# gateway.net
KiCad netlist of a schematic drawn in Altium Designer
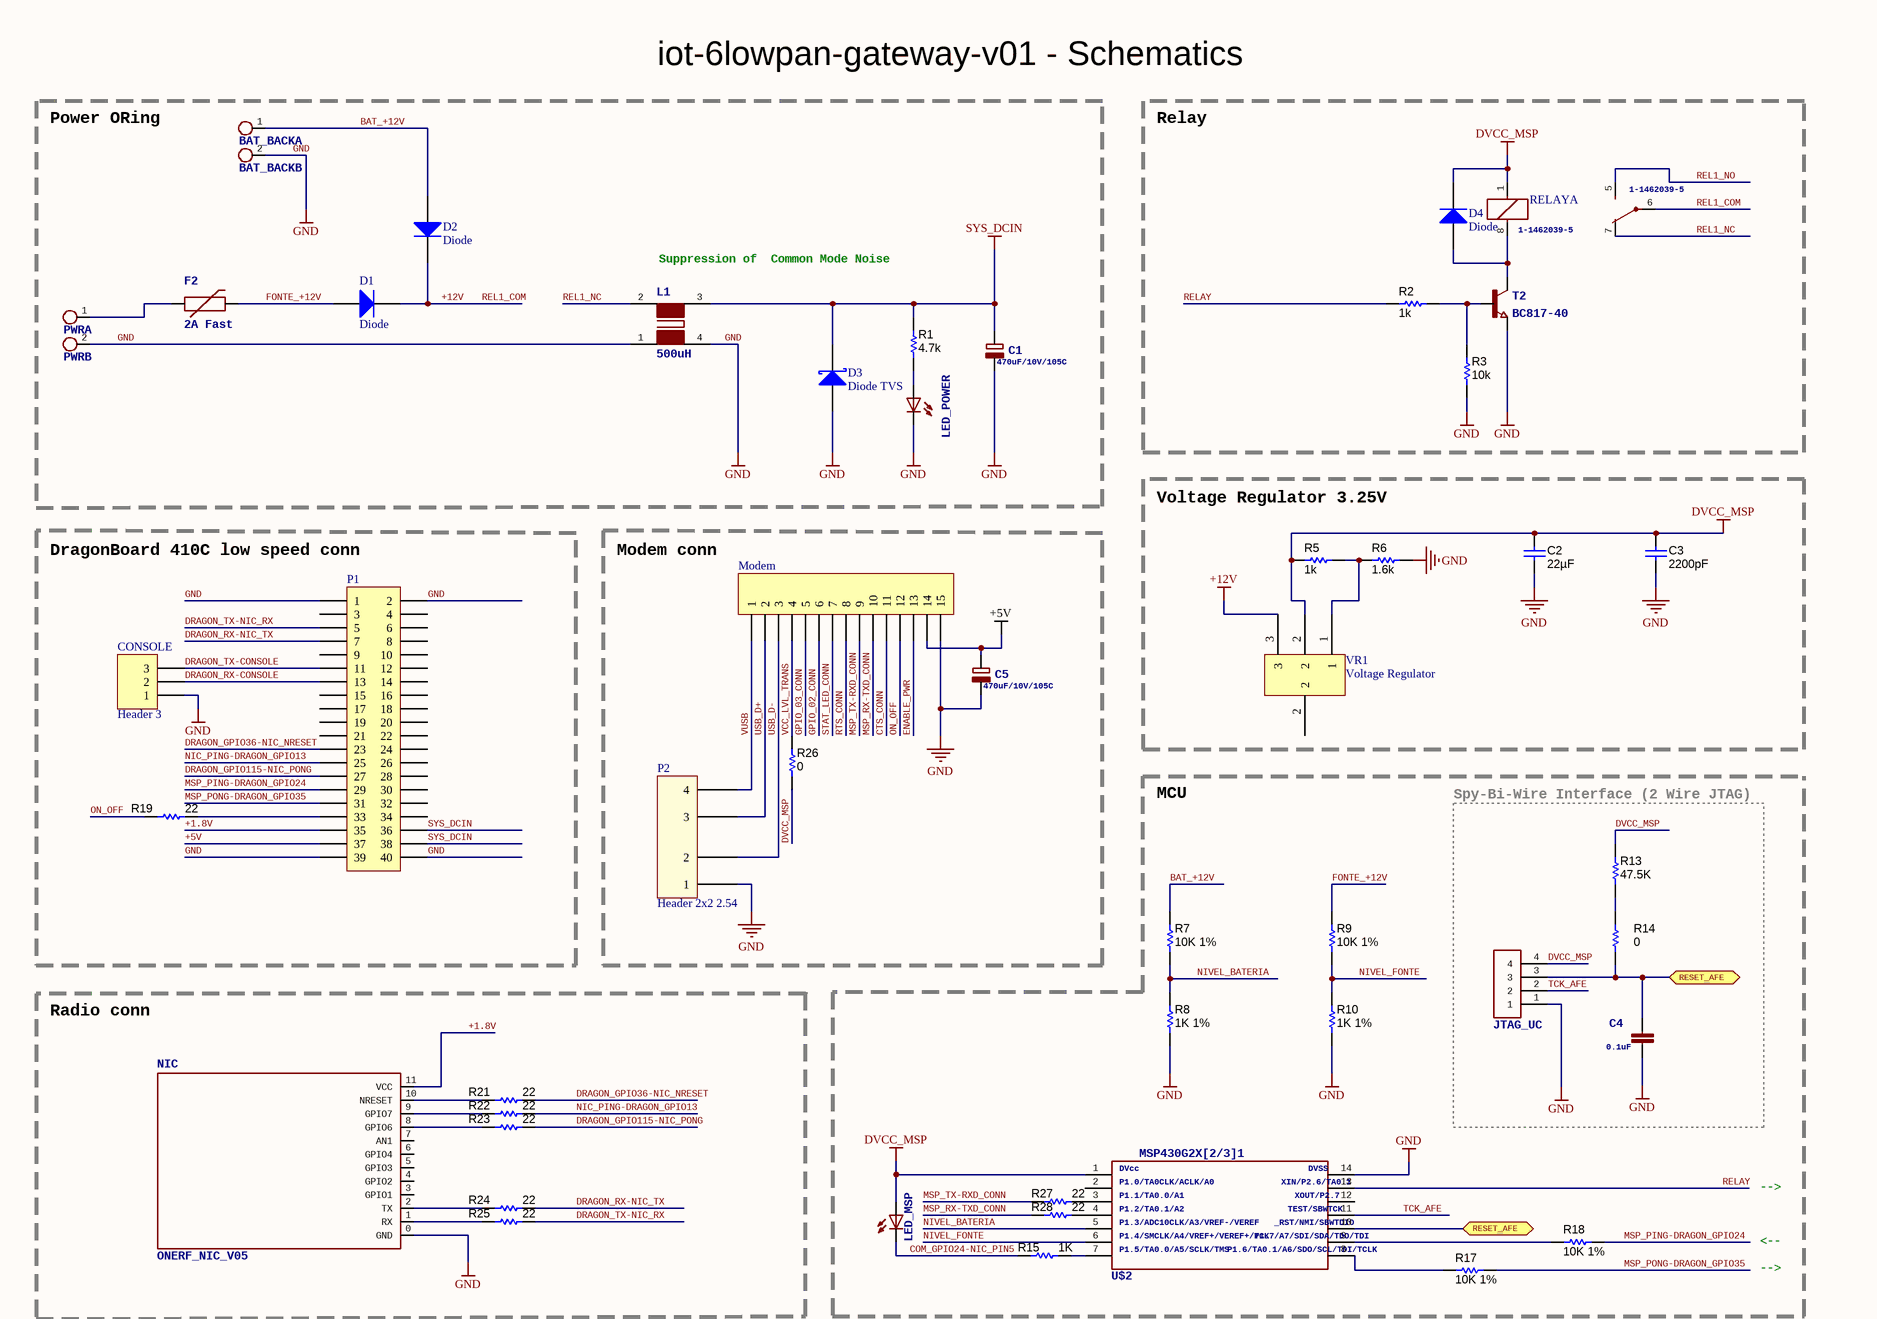
[diagram p0: gateway.SchDoc, top]
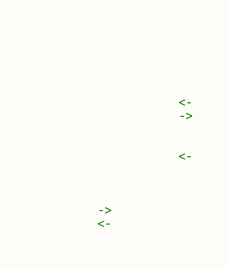
[diagram p1: gateway.SchDoc, bottom]

(export (version "E")
  (design (tool "Eeschema 10.0.6"))
  (components
    (comp (ref "BAT_BACK")
      (value "MKDSN1,5/2-5,08")
      (footprint "MKDSN1,5/2-5,08")
      (libsource (lib "Shield_Dragon") (part "MKDSN1,5/2-5,08"))
    )
    (comp (ref "C1")
      (value "470uF/10V/105C")
      (footprint "E2,5-6,3")
      (description "POLARIZED CAPACITOR, European symbol")
      (libsource (lib "oneRF_Base_COM_v04") (part "CPOL-EUE2.5-6.3"))
    )
    (comp (ref "C2")
      (value "C2012X5R1C226K125AC")
      (footprint "0805_HV")
      (description "CAP, CERM, 22 µF, 16 V, +/- 10%, X5R, 0805")
      (fields (field (name "VALUEDISPLAYED") "22µF"))
      (libsource (lib "Capacitor_Ceramic") (part "C2012X5R1C226K125AC"))
    )
    (comp (ref "C3")
      (value "CL10B222KB8SFNC")
      (footprint "0603")
      (description "CAP, CERM, 2200 pF, 50 V, +/- 10%, X7R, 0603")
      (fields (field (name "VALUEDISPLAYED") "2200pF") (field (name "PUBLISHER") "Texas Instruments"))
      (libsource (lib "altium-import") (part "root_3_C1005X7R1H222K_"))
    )
    (comp (ref "C4")
      (value "0.1uF")
      (footprint "0603")
      (description "CAPACITOR, European symbol")
      (libsource (lib "rcl") (part "C-EUC0603_DWS"))
    )
    (comp (ref "C5")
      (value "470uF/10V/105C")
      (footprint "E2,5-6,3")
      (description "POLARIZED CAPACITOR, European symbol")
      (libsource (lib "oneRF_Base_COM_v04") (part "CPOL-EUE2.5-6.3"))
    )
    (comp (ref "CONSOLE")
      (value "Header 3")
      (footprint "HDR1X3")
      (description "Header, 3-Pin")
      (fields (field (name "PUBLISHER") "Altium Limited"))
      (libsource (lib "Miscellaneous Connectors") (part "Header 3"))
    )
    (comp (ref "D1")
      (value "Diode")
      (footprint "SOD-80")
      (description "Diode, 100v, 1V, 200mA, -65º, 175º, SMT")
      (fields (field (name "PARTNUMBER") "FDLL4148_D87Z"))
      (libsource (lib "Miscellaneous Devices") (part "Diode"))
    )
    (comp (ref "D2")
      (value "Diode")
      (footprint "SOD-80")
      (description "Diode, 100v, 1V, 200mA, -65º, 175º, SMT")
      (fields (field (name "PARTNUMBER") "FDLL4148_D87Z"))
      (libsource (lib "Miscellaneous Devices") (part "Diode"))
    )
    (comp (ref "D3")
      (value "Diode TVS")
      (footprint "SMB")
      (description "Schottky Diode")
      (fields (field (name "PUBLISHER") "Altium Limited"))
      (libsource (lib "Miscellaneous Devices") (part "D Schottky"))
    )
    (comp (ref "D4")
      (value "Diode")
      (footprint "SOD-80")
      (description "Diode, 100v, 1V, 200mA, -65º, 175º, SMT")
      (fields (field (name "PARTNUMBER") "FDLL4148_D87Z"))
      (libsource (lib "Miscellaneous Devices") (part "Diode"))
    )
    (comp (ref "F2")
      (value "2A Fast")
      (footprint "C1206")
      (description "Resettable Fuse PTCResettable Fuse. Spark Fun Electronics SKU : COM-08357")
      (libsource (lib "SparkFun-PowerIC") (part "PTCSMD-W"))
    )
    (comp (ref "JTAG_UC")
      (value "CONECTOR_1X042.54MM")
      (footprint "HDR1X4")
      (libsource (lib "sparkFun2") (part "CONECTOR_1X042.54MM"))
    )
    (comp (ref "L1")
      (value "500uH")
      (footprint "WE-SL2_74422...")
      (libsource (lib "qualified_1") (part "WE-SL2"))
    )
    (comp (ref "LED_MSP")
      (value "LED/WHITE/0603")
      (footprint "LED0603")
      (libsource (lib "Shield_Dragon") (part "LED0603_WWS"))
    )
    (comp (ref "LED_POWER")
      (value "LED/Red/0603")
      (footprint "LED0603")
      (libsource (lib "Shield_Dragon") (part "LED0603DWS"))
    )
    (comp (ref "Modem")
      (value "oneRF_Modem_v01")
      (footprint "oneRF_Modem_v01")
      (description "CONN HEADER .100\" SNGL STR 15POS")
      (fields
        (field (name "MANUFACTURER") "Wurth Electronics Inc.")
        (field (name "MANUFACTURER PART NUMBER") "61301511121")
      )
      (libsource (lib "Schlib1 - copy") (part "Header 15"))
    )
    (comp (ref "NIC")
      (value "ONERF_NIC_V05")
      (footprint "ONERF_NIC_V05")
      (libsource (lib "oneRF_Base_COM_v04") (part "ONERF_NIC_V05"))
    )
    (comp (ref "P1")
      (value "Header 20X2")
      (footprint "HDR2X20")
      (description "Header, 20-Pin, Dual row")
      (fields (field (name "PUBLISHER") "Altium Limited"))
      (libsource (lib "Miscellaneous Connectors") (part "Header 20X2"))
    )
    (comp (ref "P2")
      (value "Header 2x2 2.54")
      (footprint "HEADER2x2(2.54)")
      (libsource (lib "Shield_Dragon") (part "HEADER2x2(2.54)"))
    )
    (comp (ref "PWR")
      (value "MKDSN1,5/2-5,08")
      (footprint "MKDSN1,5/2-5,08")
      (libsource (lib "Shield_Dragon") (part "MKDSN1,5/2-5,08"))
    )
    (comp (ref "R1")
      (value "4.7k")
      (footprint "0603")
      (description "RES, 1kohm, 1%, 1/10W, 0603")
      (fields (field (name "PARTNUMBER") "CRCW06031K00FKEA"))
      (libsource (lib "MiscParts") (part "Resistor"))
    )
    (comp (ref "R2")
      (value "1k")
      (footprint "0603")
      (description "RES, 1kohm, 1%, 1/10W, 0603")
      (fields (field (name "PARTNUMBER") "CRCW06031K00FKEA"))
      (libsource (lib "MiscParts") (part "Resistor"))
    )
    (comp (ref "R3")
      (value "10k")
      (footprint "0603")
      (description "RES, 1kohm, 1%, 1/10W, 0603")
      (fields (field (name "PARTNUMBER") "CRCW06031K00FKEA"))
      (libsource (lib "MiscParts") (part "Resistor"))
    )
    (comp (ref "R5")
      (value "1k")
      (footprint "0603")
      (description "RES, 1kohm, 1%, 1/10W, 0603")
      (fields (field (name "PARTNUMBER") "CRCW06031K00FKEA"))
      (libsource (lib "MiscParts") (part "Resistor"))
    )
    (comp (ref "R6")
      (value "1.6k")
      (footprint "0603")
      (description "RES, 1.6kohm, 1%, 1/10W, 0603")
      (fields (field (name "PARTNUMBER") "RC0603FR-071K6L"))
      (libsource (lib "MiscParts") (part "Resistor"))
    )
    (comp (ref "R7")
      (value "10K 1%")
      (footprint "0603")
      (description "RES, 1kohm, 1%, 1/10W, 0603")
      (fields (field (name "PARTNUMBER") "CRCW06031K00FKEA"))
      (libsource (lib "MiscParts") (part "Resistor"))
    )
    (comp (ref "R8")
      (value "1K 1%")
      (footprint "0603")
      (description "RES, 1kohm, 1%, 1/10W, 0603")
      (fields (field (name "PARTNUMBER") "CRCW06031K00FKEA"))
      (libsource (lib "MiscParts") (part "Resistor"))
    )
    (comp (ref "R9")
      (value "10K 1%")
      (footprint "0603")
      (description "RES, 1kohm, 1%, 1/10W, 0603")
      (fields (field (name "PARTNUMBER") "CRCW06031K00FKEA"))
      (libsource (lib "MiscParts") (part "Resistor"))
    )
    (comp (ref "R10")
      (value "1K 1%")
      (footprint "0603")
      (description "RES, 1kohm, 1%, 1/10W, 0603")
      (fields (field (name "PARTNUMBER") "CRCW06031K00FKEA"))
      (libsource (lib "MiscParts") (part "Resistor"))
    )
    (comp (ref "R13")
      (value "47.5K")
      (footprint "0603")
      (description "RES, 1kohm, 1%, 1/10W, 0603")
      (fields (field (name "PARTNUMBER") "CRCW06031K00FKEA"))
      (libsource (lib "MiscParts") (part "Resistor"))
    )
    (comp (ref "R14")
      (value "0")
      (footprint "0603")
      (description "RES, 1kohm, 1%, 1/10W, 0603")
      (fields (field (name "PARTNUMBER") "CRCW06031K00FKEA"))
      (libsource (lib "MiscParts") (part "Resistor"))
    )
    (comp (ref "R15")
      (value "1K")
      (footprint "0603")
      (description "RES, 1kohm, 1%, 1/10W, 0603")
      (fields (field (name "PARTNUMBER") "CRCW06031K00FKEA"))
      (libsource (lib "MiscParts") (part "Resistor"))
    )
    (comp (ref "R17")
      (value "10K 1%")
      (footprint "0603")
      (description "RES, 1kohm, 1%, 1/10W, 0603")
      (fields (field (name "PARTNUMBER") "CRCW06031K00FKEA"))
      (libsource (lib "MiscParts") (part "Resistor"))
    )
    (comp (ref "R18")
      (value "10K 1%")
      (footprint "0603")
      (description "RES, 1kohm, 1%, 1/10W, 0603")
      (fields (field (name "PARTNUMBER") "CRCW06031K00FKEA"))
      (libsource (lib "MiscParts") (part "Resistor"))
    )
    (comp (ref "R19")
      (value "22")
      (footprint "0603")
      (description "RES, 1kohm, 1%, 1/10W, 0603")
      (fields (field (name "PARTNUMBER") "CRCW06031K00FKEA"))
      (libsource (lib "MiscParts") (part "Resistor"))
    )
    (comp (ref "R21")
      (value "22")
      (footprint "0603")
      (description "RES, 1kohm, 1%, 1/10W, 0603")
      (fields (field (name "PARTNUMBER") "CRCW06031K00FKEA"))
      (libsource (lib "MiscParts") (part "Resistor"))
    )
    (comp (ref "R22")
      (value "22")
      (footprint "0603")
      (description "RES, 1kohm, 1%, 1/10W, 0603")
      (fields (field (name "PARTNUMBER") "CRCW06031K00FKEA"))
      (libsource (lib "MiscParts") (part "Resistor"))
    )
    (comp (ref "R23")
      (value "22")
      (footprint "0603")
      (description "RES, 1kohm, 1%, 1/10W, 0603")
      (fields (field (name "PARTNUMBER") "CRCW06031K00FKEA"))
      (libsource (lib "MiscParts") (part "Resistor"))
    )
    (comp (ref "R24")
      (value "22")
      (footprint "0603")
      (description "RES, 1kohm, 1%, 1/10W, 0603")
      (fields (field (name "PARTNUMBER") "CRCW06031K00FKEA"))
      (libsource (lib "MiscParts") (part "Resistor"))
    )
    (comp (ref "R25")
      (value "22")
      (footprint "0603")
      (description "RES, 1kohm, 1%, 1/10W, 0603")
      (fields (field (name "PARTNUMBER") "CRCW06031K00FKEA"))
      (libsource (lib "MiscParts") (part "Resistor"))
    )
    (comp (ref "R26")
      (value "0")
      (footprint "0603")
      (description "RES, 1kohm, 1%, 1/10W, 0603")
      (fields (field (name "PARTNUMBER") "CRCW06031K00FKEA"))
      (libsource (lib "MiscParts") (part "Resistor"))
    )
    (comp (ref "R27")
      (value "22")
      (footprint "0603")
      (description "RES, 1kohm, 1%, 1/10W, 0603")
      (fields (field (name "PARTNUMBER") "CRCW06031K00FKEA"))
      (libsource (lib "MiscParts") (part "Resistor"))
    )
    (comp (ref "R28")
      (value "22")
      (footprint "0603")
      (description "RES, 1kohm, 1%, 1/10W, 0603")
      (fields (field (name "PARTNUMBER") "CRCW06031K00FKEA"))
      (libsource (lib "MiscParts") (part "Resistor"))
    )
    (comp (ref "RELAY")
      (value "1-1462039-5")
      (footprint "1-1462039-5")
      (description "RELAY")
      (libsource (lib "Shield_Dragon") (part "1-1462039-5"))
    )
    (comp (ref "T2")
      (value "BC817-40")
      (footprint "SOT23_N")
      (description "NPN TRANSISTOR")
      (libsource (lib "semicon-smd-ipc") (part "NPN-TRANSISTOR_SOT23"))
    )
    (comp (ref "U$2")
      (value "MSP430G2231")
      (footprint "PW014_N")
      (fields
        (field (name "MSP430G2X[2/3]1") "MSP430G2X[2/3]1")
        (field (name "DVCC") "DVcc")
        (field (name "P1.0/TA0CLK/ACLK/A0") "P1.0/TA0CLK/ACLK/A0")
        (field (name "P1.1/TA0.0/A1") "P1.1/TA0.0/A1")
        (field (name "P1.2/TA0.1/A2") "P1.2/TA0.1/A2")
        (field (name "P1.3/ADC10CLK/A3/VREF-/VEREF") "P1.3/ADC10CLK/A3/VREF-/VEREF")
        (field (name "P1.4/SMCLK/A4/VREF+/VEREF+/TCK") "P1.4/SMCLK/A4/VREF+/VEREF+/TCK")
        (field (name "P1.5/TA0.0/A5/SCLK/TMS") "P1.5/TA0.0/A5/SCLK/TMS")
        (field (name "P1.6/TA0.1/A6/SDO/SCL/TDI/TCLK") "P1.6/TA0.1/A6/SDO/SCL/TDI/TCLK")
        (field (name "P1.7/A7/SDI/SDA/TDO/TDI") "P1.7/A7/SDI/SDA/TDO/TDI")
        (field (name "_RST/NMI/SBWTDIO") "_RST/NMI/SBWTDIO")
        (field (name "TEST/SBWTCK") "TEST/SBWTCK")
        (field (name "XOUT/P2.7") "XOUT/P2.7")
        (field (name "XIN/P2.6/TA0.1") "XIN/P2.6/TA0.1")
        (field (name "DVSS") "DVSS")
      )
      (libsource (lib "TI_MSP430_v16") (part "G2X[2/3]1---PW14"))
    )
    (comp (ref "VR1")
      (value "Voltage Regulator")
      (footprint "SOT223")
      (fields (field (name "PARTNUMBER") "AZ1117H-ADJTRE1"))
      (libsource (lib "Shield_Dragon") (part "Voltage Regulator"))
    )
  )
  (nets
    (net (code "1") (name "+5V") (class "Default")
      (node (ref "C5") (pin "+") (pinfunction "+_+") (pintype "passive"))
      (node (ref "Modem") (pin "14") (pinfunction "14_14") (pintype "passive"))
      (node (ref "P1") (pin "37") (pinfunction "37_37") (pintype "passive"))
    )
    (net (code "2") (name "+12V") (class "Default")
      (node (ref "D1") (pin "2") (pinfunction "K_2") (pintype "passive"))
      (node (ref "D2") (pin "2") (pinfunction "K_2") (pintype "passive"))
      (node (ref "RELAY") (pin "6") (pinfunction "COM_6") (pintype "passive"))
      (node (ref "VR1") (pin "3") (pinfunction "3_3") (pintype "passive"))
    )
    (net (code "3") (name "/+1.8V") (class "Default")
      (node (ref "NIC") (pin "11") (pinfunction "VCC_11") (pintype "power_in"))
      (node (ref "P1") (pin "35") (pinfunction "35_35") (pintype "passive"))
    )
    (net (code "4") (name "/BAT_+12V") (class "Default")
      (node (ref "BAT_BACK") (pin "1") (pinfunction "KL_1") (pintype "passive"))
      (node (ref "D2") (pin "1") (pinfunction "A_1") (pintype "passive"))
      (node (ref "R7") (pin "2") (pinfunction "2_2") (pintype "passive"))
    )
    (net (code "5") (name "/COM_GPIO24-NIC_PIN5") (class "Default")
      (node (ref "LED_MSP") (pin "2") (pinfunction "C_2") (pintype "passive"))
      (node (ref "R15") (pin "2") (pinfunction "2_2") (pintype "passive"))
    )
    (net (code "6") (name "/CTS_CONN") (class "Default")
      (node (ref "Modem") (pin "11") (pinfunction "11_11") (pintype "passive"))
    )
    (net (code "7") (name "/DRAGON_GPIO36-NIC_NRESET") (class "Default")
      (node (ref "P1") (pin "23") (pinfunction "23_23") (pintype "passive"))
      (node (ref "R21") (pin "1") (pinfunction "1_1") (pintype "passive"))
    )
    (net (code "8") (name "/DRAGON_GPIO115-NIC_PONG") (class "Default")
      (node (ref "P1") (pin "27") (pinfunction "27_27") (pintype "passive"))
      (node (ref "R23") (pin "1") (pinfunction "1_1") (pintype "passive"))
    )
    (net (code "9") (name "/DRAGON_RX-CONSOLE") (class "Default")
      (node (ref "CONSOLE") (pin "2") (pinfunction "2_2") (pintype "passive"))
      (node (ref "P1") (pin "13") (pinfunction "13_13") (pintype "passive"))
    )
    (net (code "10") (name "/DRAGON_RX-NIC_TX") (class "Default")
      (node (ref "P1") (pin "7") (pinfunction "7_7") (pintype "passive"))
      (node (ref "R24") (pin "1") (pinfunction "1_1") (pintype "passive"))
    )
    (net (code "11") (name "/DRAGON_TX-CONSOLE") (class "Default")
      (node (ref "CONSOLE") (pin "3") (pinfunction "3_3") (pintype "passive"))
      (node (ref "P1") (pin "11") (pinfunction "11_11") (pintype "passive"))
    )
    (net (code "12") (name "/DRAGON_TX-NIC_RX") (class "Default")
      (node (ref "P1") (pin "5") (pinfunction "5_5") (pintype "passive"))
      (node (ref "R25") (pin "1") (pinfunction "1_1") (pintype "passive"))
    )
    (net (code "13") (name "/ENABLE_PWR") (class "Default")
      (node (ref "Modem") (pin "13") (pinfunction "13_13") (pintype "passive"))
    )
    (net (code "14") (name "/FONTE_+12V") (class "Default")
      (node (ref "D1") (pin "1") (pinfunction "A_1") (pintype "passive"))
      (node (ref "F2") (pin "2") (pinfunction "2_2") (pintype "passive"))
      (node (ref "R9") (pin "2") (pinfunction "2_2") (pintype "passive"))
    )
    (net (code "15") (name "/GPIO_02_CONN") (class "Default")
      (node (ref "Modem") (pin "6") (pinfunction "6_6") (pintype "passive"))
    )
    (net (code "16") (name "/GPIO_03_CONN") (class "Default")
      (node (ref "Modem") (pin "5") (pinfunction "5_5") (pintype "passive"))
    )
    (net (code "17") (name "/MSP_PING-DRAGON_GPIO24") (class "Default")
      (node (ref "P1") (pin "29") (pinfunction "29_29") (pintype "passive"))
      (node (ref "R18") (pin "1") (pinfunction "1_1") (pintype "passive"))
    )
    (net (code "18") (name "/MSP_PONG-DRAGON_GPIO35") (class "Default")
      (node (ref "P1") (pin "31") (pinfunction "31_31") (pintype "passive"))
      (node (ref "R17") (pin "1") (pinfunction "1_1") (pintype "passive"))
    )
    (net (code "19") (name "/MSP_RX-TXD_CONN") (class "Default")
      (node (ref "Modem") (pin "10") (pinfunction "10_10") (pintype "passive"))
      (node (ref "R28") (pin "2") (pinfunction "2_2") (pintype "passive"))
    )
    (net (code "20") (name "/MSP_TX-RXD_CONN") (class "Default")
      (node (ref "Modem") (pin "9") (pinfunction "9_9") (pintype "passive"))
      (node (ref "R27") (pin "2") (pinfunction "2_2") (pintype "passive"))
    )
    (net (code "21") (name "/NIC_PING-DRAGON_GPIO13") (class "Default")
      (node (ref "P1") (pin "25") (pinfunction "25_25") (pintype "passive"))
      (node (ref "R22") (pin "1") (pinfunction "1_1") (pintype "passive"))
    )
    (net (code "22") (name "/NIVEL_BATERIA") (class "Default")
      (node (ref "R7") (pin "1") (pinfunction "1_1") (pintype "passive"))
      (node (ref "R8") (pin "2") (pinfunction "2_2") (pintype "passive"))
      (node (ref "U$2") (pin "5") (pinfunction "5_5") (pintype "passive"))
    )
    (net (code "23") (name "/NIVEL_FONTE") (class "Default")
      (node (ref "R10") (pin "2") (pinfunction "2_2") (pintype "passive"))
      (node (ref "R9") (pin "1") (pinfunction "1_1") (pintype "passive"))
      (node (ref "U$2") (pin "6") (pinfunction "6_6") (pintype "passive"))
    )
    (net (code "24") (name "/ON_OFF") (class "Default")
      (node (ref "Modem") (pin "12") (pinfunction "12_12") (pintype "passive"))
      (node (ref "R19") (pin "2") (pinfunction "2_2") (pintype "passive"))
    )
    (net (code "25") (name "/REL1_NC") (class "Default")
      (node (ref "L1") (pin "2") (pinfunction "1_2") (pintype "passive"))
      (node (ref "RELAY") (pin "7") (pinfunction "NC_7") (pintype "passive"))
    )
    (net (code "26") (name "/REL1_NO") (class "Default")
      (node (ref "RELAY") (pin "5") (pinfunction "NO_5") (pintype "passive"))
    )
    (net (code "27") (name "/RELAY") (class "Default")
      (node (ref "R2") (pin "2") (pinfunction "2_2") (pintype "passive"))
      (node (ref "U$2") (pin "13") (pinfunction "13_13") (pintype "passive"))
    )
    (net (code "28") (name "/RESET_AFE") (class "Default")
      (node (ref "C4") (pin "1") (pinfunction "1_1") (pintype "passive"))
      (node (ref "JTAG_UC") (pin "3") (pinfunction "3_3") (pintype "passive"))
      (node (ref "R14") (pin "1") (pinfunction "1_1") (pintype "passive"))
      (node (ref "U$2") (pin "10") (pinfunction "10_10") (pintype "passive"))
    )
    (net (code "29") (name "/RTS_CONN") (class "Default")
      (node (ref "Modem") (pin "8") (pinfunction "8_8") (pintype "passive"))
    )
    (net (code "30") (name "/STAT_LED_CONN") (class "Default")
      (node (ref "Modem") (pin "7") (pinfunction "7_7") (pintype "passive"))
    )
    (net (code "31") (name "/TCK_AFE") (class "Default")
      (node (ref "JTAG_UC") (pin "2") (pinfunction "2_2") (pintype "passive"))
      (node (ref "U$2") (pin "11") (pinfunction "11_11") (pintype "passive"))
    )
    (net (code "32") (name "/USB_D+") (class "Default")
      (node (ref "Modem") (pin "2") (pinfunction "2_2") (pintype "passive"))
      (node (ref "P2") (pin "3") (pinfunction "3_3") (pintype "passive"))
    )
    (net (code "33") (name "/USB_D-") (class "Default")
      (node (ref "Modem") (pin "3") (pinfunction "3_3") (pintype "passive"))
      (node (ref "P2") (pin "2") (pinfunction "2_2") (pintype "passive"))
    )
    (net (code "34") (name "/VCC_LVL_TRANS") (class "Default")
      (node (ref "Modem") (pin "4") (pinfunction "4_4") (pintype "passive"))
      (node (ref "R26") (pin "2") (pinfunction "2_2") (pintype "passive"))
    )
    (net (code "35") (name "/VUSB") (class "Default")
      (node (ref "Modem") (pin "1") (pinfunction "1_1") (pintype "passive"))
      (node (ref "P2") (pin "4") (pinfunction "4_4") (pintype "passive"))
    )
    (net (code "36") (name "DVCC_MSP") (class "Default")
      (node (ref "C2") (pin "1") (pinfunction "1_1") (pintype "passive"))
      (node (ref "C3") (pin "2") (pinfunction "2_2") (pintype "passive"))
      (node (ref "D4") (pin "2") (pinfunction "K_2") (pintype "passive"))
      (node (ref "JTAG_UC") (pin "4") (pinfunction "4_4") (pintype "passive"))
      (node (ref "LED_MSP") (pin "1") (pinfunction "A_1") (pintype "passive"))
      (node (ref "R13") (pin "2") (pinfunction "2_2") (pintype "passive"))
      (node (ref "R26") (pin "1") (pinfunction "1_1") (pintype "passive"))
      (node (ref "R5") (pin "1") (pinfunction "1_1") (pintype "passive"))
      (node (ref "RELAY") (pin "1") (pinfunction "1_1") (pintype "passive"))
      (node (ref "U$2") (pin "1") (pinfunction "1_1") (pintype "passive"))
      (node (ref "VR1") (pin "2") (pinfunction "2_2") (pintype "passive"))
    )
    (net (code "37") (name "GND") (class "Default")
      (node (ref "BAT_BACK") (pin "2") (pinfunction "KL_2") (pintype "passive"))
      (node (ref "C1") (pin "-") (pinfunction "-_-") (pintype "passive"))
      (node (ref "C2") (pin "2") (pinfunction "2_2") (pintype "passive"))
      (node (ref "C3") (pin "1") (pinfunction "1_1") (pintype "passive"))
      (node (ref "C4") (pin "2") (pinfunction "2_2") (pintype "passive"))
      (node (ref "C5") (pin "-") (pinfunction "-_-") (pintype "passive"))
      (node (ref "CONSOLE") (pin "1") (pinfunction "1_1") (pintype "passive"))
      (node (ref "D3") (pin "1") (pinfunction "A_1") (pintype "passive"))
      (node (ref "JTAG_UC") (pin "1") (pinfunction "1_1") (pintype "passive"))
      (node (ref "L1") (pin "1") (pinfunction "2_1") (pintype "passive"))
      (node (ref "L1") (pin "4") (pinfunction "3_4") (pintype "passive"))
      (node (ref "LED_POWER") (pin "2") (pinfunction "C_2") (pintype "passive"))
      (node (ref "Modem") (pin "15") (pinfunction "15_15") (pintype "passive"))
      (node (ref "NIC") (pin "0") (pinfunction "GND_0") (pintype "power_in"))
      (node (ref "P1") (pin "1") (pinfunction "1_1") (pintype "passive"))
      (node (ref "P1") (pin "2") (pinfunction "2_2") (pintype "passive"))
      (node (ref "P1") (pin "39") (pinfunction "39_39") (pintype "passive"))
      (node (ref "P1") (pin "40") (pinfunction "40_40") (pintype "passive"))
      (node (ref "P2") (pin "1") (pinfunction "1_1") (pintype "passive"))
      (node (ref "PWR") (pin "2") (pinfunction "KL_2") (pintype "passive"))
      (node (ref "R10") (pin "1") (pinfunction "1_1") (pintype "passive"))
      (node (ref "R3") (pin "1") (pinfunction "1_1") (pintype "passive"))
      (node (ref "R6") (pin "2") (pinfunction "2_2") (pintype "passive"))
      (node (ref "R8") (pin "1") (pinfunction "1_1") (pintype "passive"))
      (node (ref "T2") (pin "2") (pinfunction "E_2") (pintype "passive"))
      (node (ref "U$2") (pin "14") (pinfunction "14_14") (pintype "passive"))
    )
    (net (code "38") (name "Net-(D4-A)") (class "Default")
      (node (ref "D4") (pin "1") (pinfunction "A_1") (pintype "passive"))
      (node (ref "RELAY") (pin "8") (pinfunction "8_8") (pintype "passive"))
      (node (ref "T2") (pin "3") (pinfunction "C_3") (pintype "passive"))
    )
    (net (code "39") (name "Net-(LED_POWER-A)") (class "Default")
      (node (ref "LED_POWER") (pin "1") (pinfunction "A_1") (pintype "passive"))
      (node (ref "R1") (pin "1") (pinfunction "1_1") (pintype "passive"))
    )
    (net (code "40") (name "Net-(NIC-GPIO6)") (class "Default")
      (node (ref "NIC") (pin "8") (pinfunction "GPIO6_8") (pintype "passive"))
      (node (ref "R23") (pin "2") (pinfunction "2_2") (pintype "passive"))
    )
    (net (code "41") (name "Net-(NIC-GPIO7)") (class "Default")
      (node (ref "NIC") (pin "9") (pinfunction "GPIO7_9") (pintype "passive"))
      (node (ref "R22") (pin "2") (pinfunction "2_2") (pintype "passive"))
    )
    (net (code "42") (name "Net-(NIC-NRESET)") (class "Default")
      (node (ref "NIC") (pin "10") (pinfunction "NRESET_10") (pintype "passive"))
      (node (ref "R21") (pin "2") (pinfunction "2_2") (pintype "passive"))
    )
    (net (code "43") (name "Net-(NIC-RX)") (class "Default")
      (node (ref "NIC") (pin "1") (pinfunction "RX_1") (pintype "passive"))
      (node (ref "R25") (pin "2") (pinfunction "2_2") (pintype "passive"))
    )
    (net (code "44") (name "Net-(NIC-TX)") (class "Default")
      (node (ref "NIC") (pin "2") (pinfunction "TX_2") (pintype "passive"))
      (node (ref "R24") (pin "2") (pinfunction "2_2") (pintype "passive"))
    )
    (net (code "45") (name "Net-(P1-Pad33)") (class "Default")
      (node (ref "P1") (pin "33") (pinfunction "33_33") (pintype "passive"))
      (node (ref "R19") (pin "1") (pinfunction "1_1") (pintype "passive"))
    )
    (net (code "46") (name "Net-(PWRA-KL)") (class "Default")
      (node (ref "F2") (pin "1") (pinfunction "1_1") (pintype "passive"))
      (node (ref "PWR") (pin "1") (pinfunction "KL_1") (pintype "passive"))
    )
    (net (code "47") (name "Net-(R5-Pad2)") (class "Default")
      (node (ref "R5") (pin "2") (pinfunction "2_2") (pintype "passive"))
      (node (ref "R6") (pin "1") (pinfunction "1_1") (pintype "passive"))
      (node (ref "VR1") (pin "1") (pinfunction "1_1") (pintype "passive"))
    )
    (net (code "48") (name "Net-(R13-Pad1)") (class "Default")
      (node (ref "R13") (pin "1") (pinfunction "1_1") (pintype "passive"))
      (node (ref "R14") (pin "2") (pinfunction "2_2") (pintype "passive"))
    )
    (net (code "49") (name "Net-(R15-Pad1)") (class "Default")
      (node (ref "R15") (pin "1") (pinfunction "1_1") (pintype "passive"))
      (node (ref "U$2") (pin "7") (pinfunction "7_7") (pintype "passive"))
    )
    (net (code "50") (name "Net-(R17-Pad2)") (class "Default")
      (node (ref "R17") (pin "2") (pinfunction "2_2") (pintype "passive"))
      (node (ref "U$2") (pin "8") (pinfunction "8_8") (pintype "passive"))
    )
    (net (code "51") (name "Net-(R18-Pad2)") (class "Default")
      (node (ref "R18") (pin "2") (pinfunction "2_2") (pintype "passive"))
      (node (ref "U$2") (pin "9") (pinfunction "9_9") (pintype "passive"))
    )
    (net (code "52") (name "Net-(R27-Pad1)") (class "Default")
      (node (ref "R27") (pin "1") (pinfunction "1_1") (pintype "passive"))
      (node (ref "U$2") (pin "3") (pinfunction "3_3") (pintype "passive"))
    )
    (net (code "53") (name "Net-(R28-Pad1)") (class "Default")
      (node (ref "R28") (pin "1") (pinfunction "1_1") (pintype "passive"))
      (node (ref "U$2") (pin "4") (pinfunction "4_4") (pintype "passive"))
    )
    (net (code "54") (name "Net-(T2-B)") (class "Default")
      (node (ref "R2") (pin "1") (pinfunction "1_1") (pintype "passive"))
      (node (ref "R3") (pin "2") (pinfunction "2_2") (pintype "passive"))
      (node (ref "T2") (pin "1") (pinfunction "B_1") (pintype "passive"))
    )
    (net (code "55") (name "SYS_DCIN") (class "Default")
      (node (ref "C1") (pin "+") (pinfunction "+_+") (pintype "passive"))
      (node (ref "D3") (pin "2") (pinfunction "K_2") (pintype "passive"))
      (node (ref "L1") (pin "3") (pinfunction "4_3") (pintype "passive"))
      (node (ref "P1") (pin "36") (pinfunction "36_36") (pintype "passive"))
      (node (ref "P1") (pin "38") (pinfunction "38_38") (pintype "passive"))
      (node (ref "R1") (pin "2") (pinfunction "2_2") (pintype "passive"))
    )
    (net (code "56") (name "unconnected-(NIC-AN1-Pad7)") (class "Default")
      (node (ref "NIC") (pin "7") (pinfunction "AN1_7") (pintype "passive"))
    )
    (net (code "57") (name "unconnected-(NIC-GPIO1-Pad3)") (class "Default")
      (node (ref "NIC") (pin "3") (pinfunction "GPIO1_3") (pintype "passive"))
    )
    (net (code "58") (name "unconnected-(NIC-GPIO2-Pad4)") (class "Default")
      (node (ref "NIC") (pin "4") (pinfunction "GPIO2_4") (pintype "passive"))
    )
    (net (code "59") (name "unconnected-(NIC-GPIO3-Pad5)") (class "Default")
      (node (ref "NIC") (pin "5") (pinfunction "GPIO3_5") (pintype "passive"))
    )
    (net (code "60") (name "unconnected-(NIC-GPIO4-Pad6)") (class "Default")
      (node (ref "NIC") (pin "6") (pinfunction "GPIO4_6") (pintype "passive"))
    )
    (net (code "61") (name "unconnected-(P1-Pad3)") (class "Default")
      (node (ref "P1") (pin "3") (pinfunction "3_3") (pintype "passive"))
    )
    (net (code "62") (name "unconnected-(P1-Pad4)") (class "Default")
      (node (ref "P1") (pin "4") (pinfunction "4_4") (pintype "passive"))
    )
    (net (code "63") (name "unconnected-(P1-Pad6)") (class "Default")
      (node (ref "P1") (pin "6") (pinfunction "6_6") (pintype "passive"))
    )
    (net (code "64") (name "unconnected-(P1-Pad8)") (class "Default")
      (node (ref "P1") (pin "8") (pinfunction "8_8") (pintype "passive"))
    )
    (net (code "65") (name "unconnected-(P1-Pad9)") (class "Default")
      (node (ref "P1") (pin "9") (pinfunction "9_9") (pintype "passive"))
    )
    (net (code "66") (name "unconnected-(P1-Pad10)") (class "Default")
      (node (ref "P1") (pin "10") (pinfunction "10_10") (pintype "passive"))
    )
    (net (code "67") (name "unconnected-(P1-Pad12)") (class "Default")
      (node (ref "P1") (pin "12") (pinfunction "12_12") (pintype "passive"))
    )
    (net (code "68") (name "unconnected-(P1-Pad14)") (class "Default")
      (node (ref "P1") (pin "14") (pinfunction "14_14") (pintype "passive"))
    )
    (net (code "69") (name "unconnected-(P1-Pad15)") (class "Default")
      (node (ref "P1") (pin "15") (pinfunction "15_15") (pintype "passive"))
    )
    (net (code "70") (name "unconnected-(P1-Pad16)") (class "Default")
      (node (ref "P1") (pin "16") (pinfunction "16_16") (pintype "passive"))
    )
    (net (code "71") (name "unconnected-(P1-Pad17)") (class "Default")
      (node (ref "P1") (pin "17") (pinfunction "17_17") (pintype "passive"))
    )
    (net (code "72") (name "unconnected-(P1-Pad18)") (class "Default")
      (node (ref "P1") (pin "18") (pinfunction "18_18") (pintype "passive"))
    )
    (net (code "73") (name "unconnected-(P1-Pad19)") (class "Default")
      (node (ref "P1") (pin "19") (pinfunction "19_19") (pintype "passive"))
    )
    (net (code "74") (name "unconnected-(P1-Pad20)") (class "Default")
      (node (ref "P1") (pin "20") (pinfunction "20_20") (pintype "passive"))
    )
    (net (code "75") (name "unconnected-(P1-Pad21)") (class "Default")
      (node (ref "P1") (pin "21") (pinfunction "21_21") (pintype "passive"))
    )
    (net (code "76") (name "unconnected-(P1-Pad22)") (class "Default")
      (node (ref "P1") (pin "22") (pinfunction "22_22") (pintype "passive"))
    )
    (net (code "77") (name "unconnected-(P1-Pad24)") (class "Default")
      (node (ref "P1") (pin "24") (pinfunction "24_24") (pintype "passive"))
    )
    (net (code "78") (name "unconnected-(P1-Pad26)") (class "Default")
      (node (ref "P1") (pin "26") (pinfunction "26_26") (pintype "passive"))
    )
    (net (code "79") (name "unconnected-(P1-Pad28)") (class "Default")
      (node (ref "P1") (pin "28") (pinfunction "28_28") (pintype "passive"))
    )
    (net (code "80") (name "unconnected-(P1-Pad30)") (class "Default")
      (node (ref "P1") (pin "30") (pinfunction "30_30") (pintype "passive"))
    )
    (net (code "81") (name "unconnected-(P1-Pad32)") (class "Default")
      (node (ref "P1") (pin "32") (pinfunction "32_32") (pintype "passive"))
    )
    (net (code "82") (name "unconnected-(P1-Pad34)") (class "Default")
      (node (ref "P1") (pin "34") (pinfunction "34_34") (pintype "passive"))
    )
    (net (code "83") (name "unconnected-(U$2-Pad2)") (class "Default")
      (node (ref "U$2") (pin "2") (pinfunction "2_2") (pintype "passive"))
    )
    (net (code "84") (name "unconnected-(U$2-Pad12)") (class "Default")
      (node (ref "U$2") (pin "12") (pinfunction "12_12") (pintype "passive"))
    )
    (net (code "85") (name "unconnected-(VR1-Pad2)") (class "Default")
      (node (ref "VR1") (pin "2") (pinfunction "2_2") (pintype "passive"))
    )
  )
)
